# mcu_valdis.net
KiCad netlist of a schematic drawn in Altium Designer
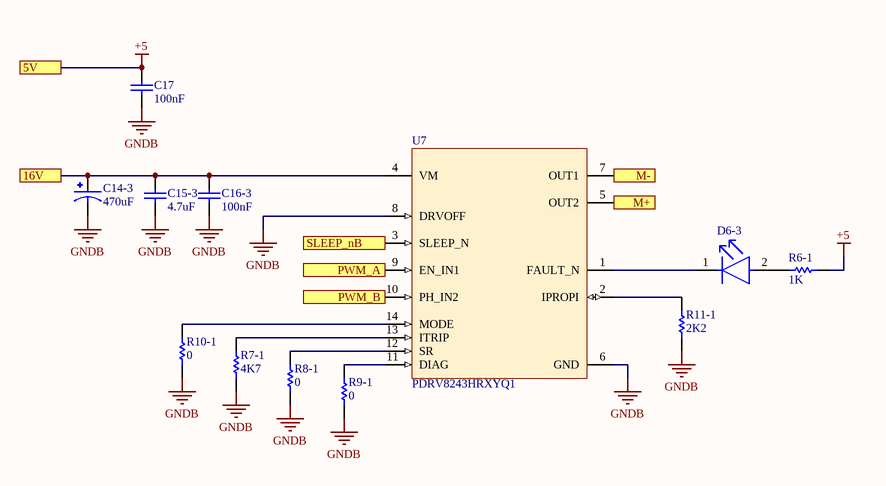
[diagram p0: mcu_valdis.SchDoc]

(export (version "E")
  (design (tool "Eeschema 10.0.6"))
  (components
    (comp (ref "C14-3")
      (value "470uF")
      (footprint "CAPPRD500W60D800H1500:CAPPRD500W60D800H1500")
      (description "470F 25V Aluminum Electrolytic Capacitors Radial, Can 8000 Hrs @ 105C")
      (fields (field (name "MF") "Panasonic") (field (name "MP") "EEUFR1E471YB"))
      (libsource (lib "pana25v470u") (part "EEUFR1E471YB"))
    )
    (comp (ref "C15-3")
      (value "4.7uF")
      (footprint "CAPC1608X90X35ML10T15")
      (description "Chip Capacitor, 22 pF, +/- 5%, 50 V, -55 to 125 degC, 0603 (1608 Metric), RoHS, Tape and Reel")
      (fields (field (name "MANUFACTURER") "Murata"))
      (libsource (lib "Altium Content Vault") (part "CAP-NP-2"))
    )
    (comp (ref "C16-3")
      (value "100nF")
      (footprint "CAPC1608X90X35ML10T15")
      (description "Chip Capacitor, 22 pF, +/- 5%, 50 V, -55 to 125 degC, 0603 (1608 Metric), RoHS, Tape and Reel")
      (fields (field (name "MANUFACTURER") "Murata"))
      (libsource (lib "Altium Content Vault") (part "CAP-NP-2"))
    )
    (comp (ref "C17")
      (value "100nF")
      (footprint "CAPC1608X90X35ML10T15")
      (description "Chip Capacitor, 22 pF, +/- 5%, 50 V, -55 to 125 degC, 0603 (1608 Metric), RoHS, Tape and Reel")
      (fields (field (name "MANUFACTURER") "Murata"))
      (libsource (lib "Altium Content Vault") (part "CAP-NP-2"))
    )
    (comp (ref "D6-3")
      (value "LTST-C191TBKT")
      (footprint "FP-LTST-C191TBKT-MFG")
      (description "LED BLUE CLEAR CHIP SMD")
      (libsource (lib "Altium Content Vault") (part "8706943c75ba83719d021d2fdc84c58"))
    )
    (comp (ref "R6-1")
      (value "1K")
      (footprint "RESC1609X50X30NL8T20")
      (description "Chip Resistor, 0 Ohm, Jumper, 100 mW, -55 to 155 degC, 0603 (1608 Metric), RoHS, Tape and Reel")
      (fields (field (name "MANUFACTURER") "Vishay Semiconductor"))
      (libsource (lib "Altium Content Vault") (part "RES-2"))
    )
    (comp (ref "R7-1")
      (value "4K7")
      (footprint "RESC1609X50X30NL8T20")
      (description "Chip Resistor, 0 Ohm, Jumper, 100 mW, -55 to 155 degC, 0603 (1608 Metric), RoHS, Tape and Reel")
      (fields (field (name "MANUFACTURER") "Vishay Semiconductor"))
      (libsource (lib "Altium Content Vault") (part "RES-2"))
    )
    (comp (ref "R8-1")
      (value "0")
      (footprint "RESC1609X50X30NL8T20")
      (description "Chip Resistor, 0 Ohm, Jumper, 100 mW, -55 to 155 degC, 0603 (1608 Metric), RoHS, Tape and Reel")
      (fields (field (name "MANUFACTURER") "Vishay Semiconductor"))
      (libsource (lib "Altium Content Vault") (part "RES-2"))
    )
    (comp (ref "R9-1")
      (value "0")
      (footprint "RESC1609X50X30NL8T20")
      (description "Chip Resistor, 0 Ohm, Jumper, 100 mW, -55 to 155 degC, 0603 (1608 Metric), RoHS, Tape and Reel")
      (fields (field (name "MANUFACTURER") "Vishay Semiconductor"))
      (libsource (lib "Altium Content Vault") (part "RES-2"))
    )
    (comp (ref "R10-1")
      (value "0")
      (footprint "RESC1609X50X30NL8T20")
      (description "Chip Resistor, 0 Ohm, Jumper, 100 mW, -55 to 155 degC, 0603 (1608 Metric), RoHS, Tape and Reel")
      (fields (field (name "MANUFACTURER") "Vishay Semiconductor"))
      (libsource (lib "Altium Content Vault") (part "RES-2"))
    )
    (comp (ref "R11-1")
      (value "2K2")
      (footprint "RESC1609X50X30NL8T20")
      (description "Chip Resistor, 0 Ohm, Jumper, 100 mW, -55 to 155 degC, 0603 (1608 Metric), RoHS, Tape and Reel")
      (fields (field (name "MANUFACTURER") "Vishay Semiconductor"))
      (libsource (lib "Altium Content Vault") (part "RES-2"))
    )
    (comp (ref "U7")
      (value "PDRV8243HRXYQ1")
      (footprint "RXY0014A-MFG")
      (description "No Description Available")
      (fields (field (name "COPYRIGHT") "Copyright (C) 2022 Ultra Librarian. All rights reserved."))
      (libsource (lib "Valdis_Components") (part "PDRV8243HRXYQ1"))
    )
  )
  (nets
    (net (code "1") (name "+5") (class "Default")
      (node (ref "C17") (pin "2") (pinfunction "2_2") (pintype "passive"))
      (node (ref "R6-1") (pin "2") (pinfunction "2_2") (pintype "passive"))
    )
    (net (code "2") (name "/16V") (class "Default")
      (node (ref "C14-3") (pin "P") (pinfunction "P_P") (pintype "passive"))
      (node (ref "C15-3") (pin "2") (pinfunction "2_2") (pintype "passive"))
      (node (ref "C16-3") (pin "2") (pinfunction "2_2") (pintype "passive"))
      (node (ref "U7") (pin "4") (pinfunction "VM_4") (pintype "power_in"))
    )
    (net (code "3") (name "/M+") (class "Default")
      (node (ref "U7") (pin "5") (pinfunction "OUT2_5") (pintype "passive"))
    )
    (net (code "4") (name "/M-") (class "Default")
      (node (ref "U7") (pin "7") (pinfunction "OUT1_7") (pintype "passive"))
    )
    (net (code "5") (name "/PWM_A") (class "Default")
      (node (ref "U7") (pin "9") (pinfunction "EN_IN1_9") (pintype "input"))
    )
    (net (code "6") (name "/PWM_B") (class "Default")
      (node (ref "U7") (pin "10") (pinfunction "PH_IN2_10") (pintype "input"))
    )
    (net (code "7") (name "/SLEEP_nB") (class "Default")
      (node (ref "U7") (pin "3") (pinfunction "SLEEP_N_3") (pintype "input"))
    )
    (net (code "8") (name "GNDB") (class "Default")
      (node (ref "C14-3") (pin "N") (pinfunction "N_N") (pintype "passive"))
      (node (ref "C15-3") (pin "1") (pinfunction "1_1") (pintype "passive"))
      (node (ref "C16-3") (pin "1") (pinfunction "1_1") (pintype "passive"))
      (node (ref "C17") (pin "1") (pinfunction "1_1") (pintype "passive"))
      (node (ref "R10-1") (pin "1") (pinfunction "1_1") (pintype "passive"))
      (node (ref "R11-1") (pin "1") (pinfunction "1_1") (pintype "passive"))
      (node (ref "R7-1") (pin "1") (pinfunction "1_1") (pintype "passive"))
      (node (ref "R8-1") (pin "1") (pinfunction "1_1") (pintype "passive"))
      (node (ref "R9-1") (pin "1") (pinfunction "1_1") (pintype "passive"))
      (node (ref "U7") (pin "6") (pinfunction "GND_6") (pintype "power_in"))
      (node (ref "U7") (pin "8") (pinfunction "DRVOFF_8") (pintype "input"))
    )
    (net (code "9") (name "Net-(D6-3-A)") (class "Default")
      (node (ref "D6-3") (pin "2") (pinfunction "A_2") (pintype "passive"))
      (node (ref "R6-1") (pin "1") (pinfunction "1_1") (pintype "passive"))
    )
    (net (code "10") (name "Net-(D6-3-C)") (class "Default")
      (node (ref "D6-3") (pin "1") (pinfunction "C_1") (pintype "passive"))
      (node (ref "U7") (pin "1") (pinfunction "FAULT_N_1") (pintype "open_collector"))
    )
    (net (code "11") (name "Net-(U7-DIAG)") (class "Default")
      (node (ref "R9-1") (pin "2") (pinfunction "2_2") (pintype "passive"))
      (node (ref "U7") (pin "11") (pinfunction "DIAG_11") (pintype "input"))
    )
    (net (code "12") (name "Net-(U7-IPROPI)") (class "Default")
      (node (ref "R11-1") (pin "2") (pinfunction "2_2") (pintype "passive"))
      (node (ref "U7") (pin "2") (pinfunction "IPROPI_2") (pintype "bidirectional"))
    )
    (net (code "13") (name "Net-(U7-ITRIP)") (class "Default")
      (node (ref "R7-1") (pin "2") (pinfunction "2_2") (pintype "passive"))
      (node (ref "U7") (pin "13") (pinfunction "ITRIP_13") (pintype "input"))
    )
    (net (code "14") (name "Net-(U7-MODE)") (class "Default")
      (node (ref "R10-1") (pin "2") (pinfunction "2_2") (pintype "passive"))
      (node (ref "U7") (pin "14") (pinfunction "MODE_14") (pintype "input"))
    )
    (net (code "15") (name "Net-(U7-SR)") (class "Default")
      (node (ref "R8-1") (pin "2") (pinfunction "2_2") (pintype "passive"))
      (node (ref "U7") (pin "12") (pinfunction "SR_12") (pintype "input"))
    )
  )
)
